# NANO_STM32F103_3.net
KiCad netlist of a schematic drawn in Altium Designer
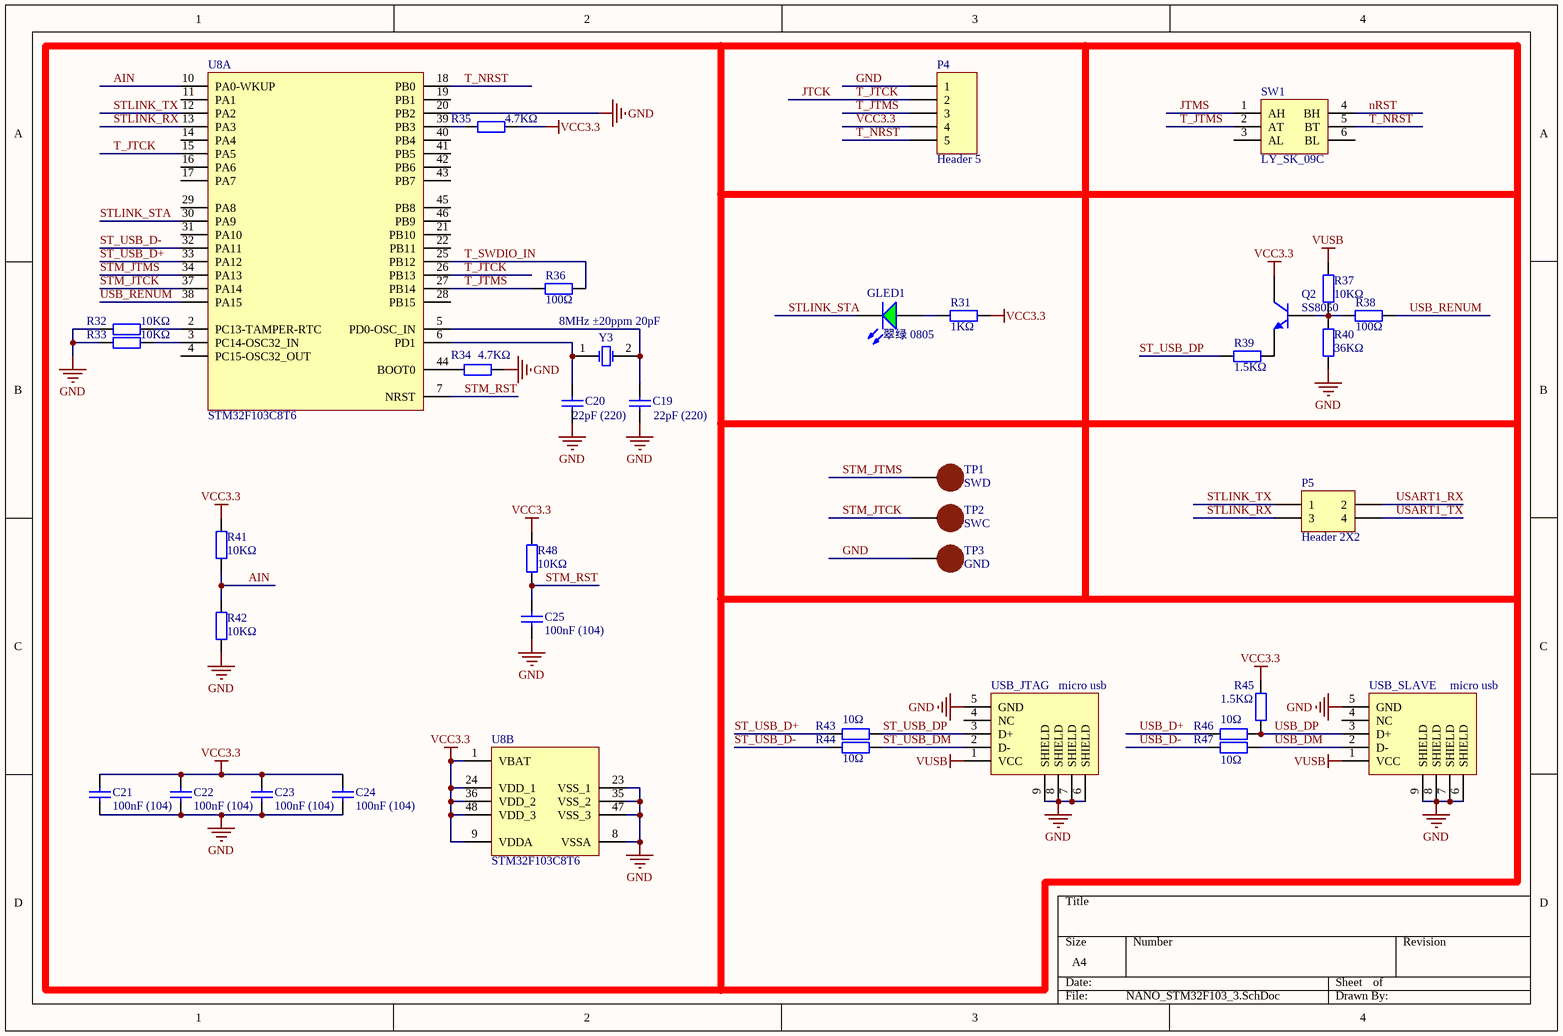
[diagram p0: NANO_STM32F103_3.SchDoc]

(export (version "E")
  (design (tool "Eeschema 10.0.6"))
  (components
    (comp (ref "C19")
      (value "22pF (220)")
      (footprint "NANO_STM32F103:0603_C")
      (description "贴片电容")
      (libsource (lib "Miscellaneous Devices LC") (part "0603 22pF (220) 5% 50V"))
    )
    (comp (ref "C20")
      (value "22pF (220)")
      (footprint "NANO_STM32F103:0603_C")
      (description "贴片电容")
      (libsource (lib "Miscellaneous Devices LC") (part "0603 22pF (220) 5% 50V"))
    )
    (comp (ref "C21")
      (value "100nF (104)")
      (footprint "NANO_STM32F103:0603_C")
      (description "贴片电容")
      (libsource (lib "Miscellaneous Devices LC") (part "0603 100nF (104) 10% 50V"))
    )
    (comp (ref "C22")
      (value "100nF (104)")
      (footprint "NANO_STM32F103:0603_C")
      (description "贴片电容")
      (libsource (lib "Miscellaneous Devices LC") (part "0603 100nF (104) 10% 50V"))
    )
    (comp (ref "C23")
      (value "100nF (104)")
      (footprint "NANO_STM32F103:0603_C")
      (description "贴片电容")
      (libsource (lib "Miscellaneous Devices LC") (part "0603 100nF (104) 10% 50V"))
    )
    (comp (ref "C24")
      (value "100nF (104)")
      (footprint "NANO_STM32F103:0603_C")
      (description "贴片电容")
      (libsource (lib "Miscellaneous Devices LC") (part "0603 100nF (104) 10% 50V"))
    )
    (comp (ref "C25")
      (value "100nF (104)")
      (footprint "NANO_STM32F103:0603_C")
      (description "贴片电容")
      (libsource (lib "Miscellaneous Devices LC") (part "0603 100nF (104) 10% 50V"))
    )
    (comp (ref "GLED1")
      (value "翠绿 0805")
      (footprint "NANO_STM32F103:0805_LED_S1")
      (description "发光二极管")
      (libsource (lib "Miscellaneous Devices LC") (part "0805 翠绿"))
    )
    (comp (ref "P4")
      (value "Header 5")
      (footprint "NANO_STM32F103:HDR1X5")
      (description "Header, 5-Pin")
      (fields (field (name "PUBLISHER") "Altium Limited"))
      (libsource (lib "Miscellaneous Connectors") (part "Header 5"))
    )
    (comp (ref "P5")
      (value "Header 2X2")
      (footprint "NANO_STM32F103:HDR2X2")
      (description "Header, 2-Pin, Dual row")
      (fields (field (name "PUBLISHER") "Altium Limited"))
      (libsource (lib "Miscellaneous Connectors") (part "Header 2X2"))
    )
    (comp (ref "Q2")
      (value "SS8050")
      (footprint "NANO_STM32F103:SOT-23(SOT-23-3)")
      (description "NPN三极管")
      (libsource (lib "Miscellaneous Devices LC") (part "SOT-23 SS8050 Y1"))
    )
    (comp (ref "R31")
      (value "1KΩ")
      (footprint "NANO_STM32F103:0603_R")
      (description "贴片电阻")
      (libsource (lib "Miscellaneous Devices LC") (part "0603 1KΩ (1001) 1%"))
    )
    (comp (ref "R32")
      (value "10KΩ")
      (footprint "NANO_STM32F103:0603_R")
      (description "贴片电阻")
      (libsource (lib "") (part "0603 10KΩ (1002) 1%_1"))
    )
    (comp (ref "R33")
      (value "10KΩ")
      (footprint "NANO_STM32F103:0603_R")
      (description "贴片电阻")
      (libsource (lib "") (part "0603 10KΩ (1002) 1%_1"))
    )
    (comp (ref "R34")
      (value "4.7KΩ")
      (footprint "NANO_STM32F103:0603_R")
      (description "贴片电阻")
      (libsource (lib "Miscellaneous Devices LC") (part "0603 4.7KΩ (4701) 1%"))
    )
    (comp (ref "R35")
      (value "4.7KΩ")
      (footprint "NANO_STM32F103:0603_R")
      (description "贴片电阻")
      (libsource (lib "Miscellaneous Devices LC") (part "0603 4.7KΩ (4701) 1%"))
    )
    (comp (ref "R36")
      (value "100Ω")
      (footprint "NANO_STM32F103:0603_R")
      (description "贴片电阻")
      (libsource (lib "Miscellaneous Devices LC") (part "0603 100Ω (1000) 1%"))
    )
    (comp (ref "R37")
      (value "10KΩ")
      (footprint "NANO_STM32F103:0603_R")
      (description "贴片电阻")
      (libsource (lib "Miscellaneous Devices LC") (part "0603 10KΩ (1002) 1%"))
    )
    (comp (ref "R38")
      (value "100Ω")
      (footprint "NANO_STM32F103:0603_R")
      (description "贴片电阻")
      (libsource (lib "Miscellaneous Devices LC") (part "0603 100Ω (1000) 1%"))
    )
    (comp (ref "R39")
      (value "1.5KΩ")
      (footprint "NANO_STM32F103:0603_R")
      (description "贴片电阻")
      (libsource (lib "") (part "0603 1.5KΩ (1501) 1%_1"))
    )
    (comp (ref "R40")
      (value "36KΩ")
      (footprint "NANO_STM32F103:0603_R")
      (description "贴片电阻")
      (libsource (lib "Miscellaneous Devices LC") (part "0603 36KΩ (3602) 1%"))
    )
    (comp (ref "R41")
      (value "10KΩ")
      (footprint "NANO_STM32F103:0603_R")
      (description "贴片电阻")
      (libsource (lib "Miscellaneous Devices LC") (part "0603 10KΩ (1002) 1%"))
    )
    (comp (ref "R42")
      (value "10KΩ")
      (footprint "NANO_STM32F103:0603_R")
      (description "贴片电阻")
      (libsource (lib "Miscellaneous Devices LC") (part "0603 10KΩ (1002) 1%"))
    )
    (comp (ref "R43")
      (value "10Ω")
      (footprint "NANO_STM32F103:0603_R")
      (description "贴片电阻")
      (libsource (lib "Miscellaneous Devices LC") (part "0603 10Ω (10R0) 1%"))
    )
    (comp (ref "R44")
      (value "10Ω")
      (footprint "NANO_STM32F103:0603_R")
      (description "贴片电阻")
      (libsource (lib "Miscellaneous Devices LC") (part "0603 10Ω (10R0) 1%"))
    )
    (comp (ref "R45")
      (value "1.5KΩ")
      (footprint "NANO_STM32F103:0603_R")
      (description "贴片电阻")
      (libsource (lib "Miscellaneous Devices LC") (part "0603 1.5KΩ (1501) 1%"))
    )
    (comp (ref "R46")
      (value "10Ω")
      (footprint "NANO_STM32F103:0603_R")
      (description "贴片电阻")
      (libsource (lib "Miscellaneous Devices LC") (part "0603 10Ω (10R0) 1%"))
    )
    (comp (ref "R47")
      (value "10Ω")
      (footprint "NANO_STM32F103:0603_R")
      (description "贴片电阻")
      (libsource (lib "Miscellaneous Devices LC") (part "0603 10Ω (10R0) 1%"))
    )
    (comp (ref "R48")
      (value "10KΩ")
      (footprint "NANO_STM32F103:0603_R")
      (description "贴片电阻")
      (libsource (lib "Miscellaneous Devices LC") (part "0603 10KΩ (1002) 1%"))
    )
    (comp (ref "SW1")
      (value "LY_SK_09C")
      (footprint "NANO_STM32F103:HDR2X3_CEN")
      (libsource (lib "NANO_STM32F103") (part "Switch_1"))
    )
    (comp (ref "TP1")
      (value "SWD")
      (footprint "NANO_STM32F103:PIN1")
      (description "圆形焊盘")
      (libsource (lib "NANO_STM32F103") (part "PAN"))
    )
    (comp (ref "TP2")
      (value "SWC")
      (footprint "NANO_STM32F103:PIN1")
      (description "圆形焊盘")
      (libsource (lib "NANO_STM32F103") (part "PAN"))
    )
    (comp (ref "TP3")
      (value "GND")
      (footprint "NANO_STM32F103:PIN1")
      (description "圆形焊盘")
      (libsource (lib "NANO_STM32F103") (part "PAN"))
    )
    (comp (ref "U8")
      (value "STM32F103C8T6")
      (footprint "NANO_STM32F103:LQFP-48_7x7x05P")
      (description "ARM")
      (libsource (lib "Miscellaneous Devices LC") (part "STM32F103C8T6"))
    )
    (comp (ref "USB_JTAG")
      (value "micro usb")
      (footprint "NANO_STM32F103:USB_Micro")
      (libsource (lib "NANO_STM32F103") (part "USB_1"))
    )
    (comp (ref "USB_SLAVE")
      (value "micro usb")
      (footprint "NANO_STM32F103:USB_Micro")
      (libsource (lib "NANO_STM32F103") (part "USB_1"))
    )
    (comp (ref "Y3")
      (value "8MHz ±20ppm 20pF")
      (footprint "NANO_STM32F103:SMD-5032_2P")
      (description "贴片晶振")
      (libsource (lib "Miscellaneous Devices LC") (part "SMD-5032_2P 8MHz 20ppm 20pF"))
    )
  )
  (nets
    (net (code "1") (name "/AIN") (class "Default")
      (node (ref "R41") (pin "1") (pinfunction "1_1") (pintype "passive"))
      (node (ref "R42") (pin "2") (pinfunction "2_2") (pintype "passive"))
      (node (ref "U8") (pin "10") (pinfunction "PA0-WKUP_10") (pintype "passive"))
    )
    (net (code "2") (name "/JTCK") (class "Default")
      (node (ref "P4") (pin "2") (pinfunction "2_2") (pintype "passive"))
      (node (ref "U8") (pin "15") (pinfunction "PA5_15") (pintype "passive"))
      (node (ref "U8") (pin "26") (pinfunction "PB13_26") (pintype "passive"))
    )
    (net (code "3") (name "/JTMS") (class "Default")
      (node (ref "SW1") (pin "1") (pinfunction "AH_1") (pintype "passive"))
    )
    (net (code "4") (name "/STLINK_RX") (class "Default")
      (node (ref "P5") (pin "3") (pinfunction "3_3") (pintype "passive"))
      (node (ref "U8") (pin "13") (pinfunction "PA3_13") (pintype "passive"))
    )
    (net (code "5") (name "/STLINK_STA") (class "Default")
      (node (ref "GLED1") (pin "K") (pinfunction "K_K") (pintype "passive"))
      (node (ref "U8") (pin "30") (pinfunction "PA9_30") (pintype "passive"))
    )
    (net (code "6") (name "/STLINK_TX") (class "Default")
      (node (ref "P5") (pin "1") (pinfunction "1_1") (pintype "passive"))
      (node (ref "U8") (pin "12") (pinfunction "PA2_12") (pintype "passive"))
    )
    (net (code "7") (name "/STM_JTCK") (class "Default")
      (node (ref "TP2") (pin "1") (pinfunction "1_1") (pintype "passive"))
      (node (ref "U8") (pin "37") (pinfunction "PA14_37") (pintype "passive"))
    )
    (net (code "8") (name "/STM_JTMS") (class "Default")
      (node (ref "TP1") (pin "1") (pinfunction "1_1") (pintype "passive"))
      (node (ref "U8") (pin "34") (pinfunction "PA13_34") (pintype "passive"))
    )
    (net (code "9") (name "/STM_RST") (class "Default")
      (node (ref "C25") (pin "1") (pinfunction "1_1") (pintype "passive"))
      (node (ref "R48") (pin "1") (pinfunction "1_1") (pintype "passive"))
      (node (ref "U8") (pin "7") (pinfunction "NRST_7") (pintype "passive"))
    )
    (net (code "10") (name "/ST_USB_D+") (class "Default")
      (node (ref "R43") (pin "1") (pinfunction "1_1") (pintype "passive"))
      (node (ref "U8") (pin "33") (pinfunction "PA12_33") (pintype "passive"))
    )
    (net (code "11") (name "/ST_USB_D-") (class "Default")
      (node (ref "R44") (pin "1") (pinfunction "1_1") (pintype "passive"))
      (node (ref "U8") (pin "32") (pinfunction "PA11_32") (pintype "passive"))
    )
    (net (code "12") (name "/ST_USB_DM") (class "Default")
      (node (ref "R44") (pin "2") (pinfunction "2_2") (pintype "passive"))
      (node (ref "USB_JTAG") (pin "2") (pinfunction "D-_2") (pintype "passive"))
    )
    (net (code "13") (name "/ST_USB_DP") (class "Default")
      (node (ref "R39") (pin "1") (pinfunction "1_1") (pintype "passive"))
      (node (ref "R43") (pin "2") (pinfunction "2_2") (pintype "passive"))
      (node (ref "USB_JTAG") (pin "3") (pinfunction "D+_3") (pintype "passive"))
    )
    (net (code "14") (name "/T_JTMS") (class "Default")
      (node (ref "P4") (pin "3") (pinfunction "3_3") (pintype "passive"))
      (node (ref "R36") (pin "1") (pinfunction "1_1") (pintype "passive"))
      (node (ref "SW1") (pin "2") (pinfunction "AT_2") (pintype "passive"))
      (node (ref "U8") (pin "27") (pinfunction "PB14_27") (pintype "passive"))
    )
    (net (code "15") (name "/T_NRST") (class "Default")
      (node (ref "P4") (pin "5") (pinfunction "5_5") (pintype "passive"))
      (node (ref "SW1") (pin "5") (pinfunction "BT_5") (pintype "passive"))
      (node (ref "U8") (pin "18") (pinfunction "PB0_18") (pintype "passive"))
    )
    (net (code "16") (name "/T_SWDIO_IN") (class "Default")
      (node (ref "R36") (pin "2") (pinfunction "2_2") (pintype "passive"))
      (node (ref "U8") (pin "25") (pinfunction "PB12_25") (pintype "passive"))
    )
    (net (code "17") (name "/USART1_RX") (class "Default")
      (node (ref "P5") (pin "2") (pinfunction "2_2") (pintype "passive"))
    )
    (net (code "18") (name "/USART1_TX") (class "Default")
      (node (ref "P5") (pin "4") (pinfunction "4_4") (pintype "passive"))
    )
    (net (code "19") (name "/USB_D+") (class "Default")
      (node (ref "R46") (pin "1") (pinfunction "1_1") (pintype "passive"))
    )
    (net (code "20") (name "/USB_D-") (class "Default")
      (node (ref "R47") (pin "1") (pinfunction "1_1") (pintype "passive"))
    )
    (net (code "21") (name "/USB_DM") (class "Default")
      (node (ref "R47") (pin "2") (pinfunction "2_2") (pintype "passive"))
      (node (ref "USB_SLAVE") (pin "2") (pinfunction "D-_2") (pintype "passive"))
    )
    (net (code "22") (name "/USB_DP") (class "Default")
      (node (ref "R45") (pin "1") (pinfunction "1_1") (pintype "passive"))
      (node (ref "R46") (pin "2") (pinfunction "2_2") (pintype "passive"))
      (node (ref "USB_SLAVE") (pin "3") (pinfunction "D+_3") (pintype "passive"))
    )
    (net (code "23") (name "/USB_RENUM") (class "Default")
      (node (ref "R38") (pin "2") (pinfunction "2_2") (pintype "passive"))
      (node (ref "U8") (pin "38") (pinfunction "PA15_38") (pintype "passive"))
    )
    (net (code "24") (name "/nRST") (class "Default")
      (node (ref "SW1") (pin "4") (pinfunction "BH_4") (pintype "passive"))
    )
    (net (code "25") (name "GND") (class "Default")
      (node (ref "C19") (pin "1") (pinfunction "1_1") (pintype "passive"))
      (node (ref "C20") (pin "1") (pinfunction "1_1") (pintype "passive"))
      (node (ref "C21") (pin "2") (pinfunction "2_2") (pintype "passive"))
      (node (ref "C22") (pin "2") (pinfunction "2_2") (pintype "passive"))
      (node (ref "C23") (pin "2") (pinfunction "2_2") (pintype "passive"))
      (node (ref "C24") (pin "2") (pinfunction "2_2") (pintype "passive"))
      (node (ref "C25") (pin "2") (pinfunction "2_2") (pintype "passive"))
      (node (ref "P4") (pin "1") (pinfunction "1_1") (pintype "passive"))
      (node (ref "R32") (pin "1") (pinfunction "1_1") (pintype "passive"))
      (node (ref "R33") (pin "1") (pinfunction "1_1") (pintype "passive"))
      (node (ref "R34") (pin "2") (pinfunction "2_2") (pintype "passive"))
      (node (ref "R40") (pin "1") (pinfunction "1_1") (pintype "passive"))
      (node (ref "R42") (pin "1") (pinfunction "1_1") (pintype "passive"))
      (node (ref "TP3") (pin "1") (pinfunction "1_1") (pintype "passive"))
      (node (ref "U8") (pin "20") (pinfunction "PB2_20") (pintype "passive"))
      (node (ref "U8") (pin "23") (pinfunction "VSS_1_23") (pintype "power_in"))
      (node (ref "U8") (pin "35") (pinfunction "VSS_2_35") (pintype "power_in"))
      (node (ref "U8") (pin "47") (pinfunction "VSS_3_47") (pintype "power_in"))
      (node (ref "U8") (pin "8") (pinfunction "VSSA_8") (pintype "power_in"))
      (node (ref "USB_JTAG") (pin "5") (pinfunction "GND_5") (pintype "passive"))
      (node (ref "USB_JTAG") (pin "6") (pinfunction "SHIELD_6") (pintype "passive"))
      (node (ref "USB_JTAG") (pin "7") (pinfunction "SHIELD_7") (pintype "passive"))
      (node (ref "USB_JTAG") (pin "8") (pinfunction "SHIELD_8") (pintype "passive"))
      (node (ref "USB_JTAG") (pin "9") (pinfunction "SHIELD_9") (pintype "passive"))
      (node (ref "USB_SLAVE") (pin "5") (pinfunction "GND_5") (pintype "passive"))
      (node (ref "USB_SLAVE") (pin "6") (pinfunction "SHIELD_6") (pintype "passive"))
      (node (ref "USB_SLAVE") (pin "7") (pinfunction "SHIELD_7") (pintype "passive"))
      (node (ref "USB_SLAVE") (pin "8") (pinfunction "SHIELD_8") (pintype "passive"))
      (node (ref "USB_SLAVE") (pin "9") (pinfunction "SHIELD_9") (pintype "passive"))
    )
    (net (code "26") (name "Net-(GLED1-PadA)") (class "Default")
      (node (ref "GLED1") (pin "A") (pinfunction "A_A") (pintype "passive"))
      (node (ref "R31") (pin "1") (pinfunction "1_1") (pintype "passive"))
    )
    (net (code "27") (name "Net-(Q2-B)") (class "Default")
      (node (ref "Q2") (pin "1") (pinfunction "B_1") (pintype "passive"))
      (node (ref "R37") (pin "1") (pinfunction "1_1") (pintype "passive"))
      (node (ref "R38") (pin "1") (pinfunction "1_1") (pintype "passive"))
      (node (ref "R40") (pin "2") (pinfunction "2_2") (pintype "passive"))
    )
    (net (code "28") (name "Net-(Q2-E)") (class "Default")
      (node (ref "Q2") (pin "2") (pinfunction "E_2") (pintype "passive"))
      (node (ref "R39") (pin "2") (pinfunction "2_2") (pintype "passive"))
    )
    (net (code "29") (name "Net-(U8A-BOOT0)") (class "Default")
      (node (ref "R34") (pin "1") (pinfunction "1_1") (pintype "passive"))
      (node (ref "U8") (pin "44") (pinfunction "BOOT0_44") (pintype "passive"))
    )
    (net (code "30") (name "Net-(U8A-PB3)") (class "Default")
      (node (ref "R35") (pin "1") (pinfunction "1_1") (pintype "passive"))
      (node (ref "U8") (pin "39") (pinfunction "PB3_39") (pintype "passive"))
    )
    (net (code "31") (name "Net-(U8A-PC13-TAMPER-RTC)") (class "Default")
      (node (ref "R32") (pin "2") (pinfunction "2_2") (pintype "passive"))
      (node (ref "U8") (pin "2") (pinfunction "PC13-TAMPER-RTC_2") (pintype "passive"))
    )
    (net (code "32") (name "Net-(U8A-PC14-OSC32_IN)") (class "Default")
      (node (ref "R33") (pin "2") (pinfunction "2_2") (pintype "passive"))
      (node (ref "U8") (pin "3") (pinfunction "PC14-OSC32_IN_3") (pintype "passive"))
    )
    (net (code "33") (name "Net-(U8A-PD0-OSC_IN)") (class "Default")
      (node (ref "C19") (pin "2") (pinfunction "2_2") (pintype "passive"))
      (node (ref "U8") (pin "5") (pinfunction "PD0-OSC_IN_5") (pintype "passive"))
      (node (ref "Y3") (pin "2") (pinfunction "OSC2_2") (pintype "passive"))
    )
    (net (code "34") (name "Net-(U8A-PD1)") (class "Default")
      (node (ref "C20") (pin "2") (pinfunction "2_2") (pintype "passive"))
      (node (ref "U8") (pin "6") (pinfunction "PD1_6") (pintype "passive"))
      (node (ref "Y3") (pin "1") (pinfunction "OSC1_1") (pintype "passive"))
    )
    (net (code "35") (name "VCC3.3") (class "Default")
      (node (ref "C21") (pin "1") (pinfunction "1_1") (pintype "passive"))
      (node (ref "C22") (pin "1") (pinfunction "1_1") (pintype "passive"))
      (node (ref "C23") (pin "1") (pinfunction "1_1") (pintype "passive"))
      (node (ref "C24") (pin "1") (pinfunction "1_1") (pintype "passive"))
      (node (ref "P4") (pin "4") (pinfunction "4_4") (pintype "passive"))
      (node (ref "Q2") (pin "3") (pinfunction "C_3") (pintype "passive"))
      (node (ref "R31") (pin "2") (pinfunction "2_2") (pintype "passive"))
      (node (ref "R35") (pin "2") (pinfunction "2_2") (pintype "passive"))
      (node (ref "R41") (pin "2") (pinfunction "2_2") (pintype "passive"))
      (node (ref "R45") (pin "2") (pinfunction "2_2") (pintype "passive"))
      (node (ref "R48") (pin "2") (pinfunction "2_2") (pintype "passive"))
      (node (ref "U8") (pin "1") (pinfunction "VBAT_1") (pintype "power_in"))
      (node (ref "U8") (pin "24") (pinfunction "VDD_1_24") (pintype "power_in"))
      (node (ref "U8") (pin "36") (pinfunction "VDD_2_36") (pintype "power_in"))
      (node (ref "U8") (pin "48") (pinfunction "VDD_3_48") (pintype "power_in"))
      (node (ref "U8") (pin "9") (pinfunction "VDDA_9") (pintype "power_in"))
    )
    (net (code "36") (name "VUSB") (class "Default")
      (node (ref "R37") (pin "2") (pinfunction "2_2") (pintype "passive"))
      (node (ref "USB_JTAG") (pin "1") (pinfunction "VCC_1") (pintype "passive"))
      (node (ref "USB_SLAVE") (pin "1") (pinfunction "VCC_1") (pintype "passive"))
    )
    (net (code "37") (name "unconnected-(SW1-AL-Pad3)") (class "Default")
      (node (ref "SW1") (pin "3") (pinfunction "AL_3") (pintype "passive"))
    )
    (net (code "38") (name "unconnected-(SW1-BL-Pad6)") (class "Default")
      (node (ref "SW1") (pin "6") (pinfunction "BL_6") (pintype "passive"))
    )
    (net (code "39") (name "unconnected-(U8A-PA1-Pad11)") (class "Default")
      (node (ref "U8") (pin "11") (pinfunction "PA1_11") (pintype "passive"))
    )
    (net (code "40") (name "unconnected-(U8A-PA4-Pad14)") (class "Default")
      (node (ref "U8") (pin "14") (pinfunction "PA4_14") (pintype "passive"))
    )
    (net (code "41") (name "unconnected-(U8A-PA6-Pad16)") (class "Default")
      (node (ref "U8") (pin "16") (pinfunction "PA6_16") (pintype "passive"))
    )
    (net (code "42") (name "unconnected-(U8A-PA7-Pad17)") (class "Default")
      (node (ref "U8") (pin "17") (pinfunction "PA7_17") (pintype "passive"))
    )
    (net (code "43") (name "unconnected-(U8A-PA8-Pad29)") (class "Default")
      (node (ref "U8") (pin "29") (pinfunction "PA8_29") (pintype "passive"))
    )
    (net (code "44") (name "unconnected-(U8A-PA10-Pad31)") (class "Default")
      (node (ref "U8") (pin "31") (pinfunction "PA10_31") (pintype "passive"))
    )
    (net (code "45") (name "unconnected-(U8A-PB1-Pad19)") (class "Default")
      (node (ref "U8") (pin "19") (pinfunction "PB1_19") (pintype "passive"))
    )
    (net (code "46") (name "unconnected-(U8A-PB4-Pad40)") (class "Default")
      (node (ref "U8") (pin "40") (pinfunction "PB4_40") (pintype "passive"))
    )
    (net (code "47") (name "unconnected-(U8A-PB5-Pad41)") (class "Default")
      (node (ref "U8") (pin "41") (pinfunction "PB5_41") (pintype "passive"))
    )
    (net (code "48") (name "unconnected-(U8A-PB6-Pad42)") (class "Default")
      (node (ref "U8") (pin "42") (pinfunction "PB6_42") (pintype "passive"))
    )
    (net (code "49") (name "unconnected-(U8A-PB7-Pad43)") (class "Default")
      (node (ref "U8") (pin "43") (pinfunction "PB7_43") (pintype "passive"))
    )
    (net (code "50") (name "unconnected-(U8A-PB8-Pad45)") (class "Default")
      (node (ref "U8") (pin "45") (pinfunction "PB8_45") (pintype "passive"))
    )
    (net (code "51") (name "unconnected-(U8A-PB9-Pad46)") (class "Default")
      (node (ref "U8") (pin "46") (pinfunction "PB9_46") (pintype "passive"))
    )
    (net (code "52") (name "unconnected-(U8A-PB10-Pad21)") (class "Default")
      (node (ref "U8") (pin "21") (pinfunction "PB10_21") (pintype "passive"))
    )
    (net (code "53") (name "unconnected-(U8A-PB11-Pad22)") (class "Default")
      (node (ref "U8") (pin "22") (pinfunction "PB11_22") (pintype "passive"))
    )
    (net (code "54") (name "unconnected-(U8A-PB15-Pad28)") (class "Default")
      (node (ref "U8") (pin "28") (pinfunction "PB15_28") (pintype "passive"))
    )
    (net (code "55") (name "unconnected-(U8A-PC15-OSC32_OUT-Pad4)") (class "Default")
      (node (ref "U8") (pin "4") (pinfunction "PC15-OSC32_OUT_4") (pintype "passive"))
    )
    (net (code "56") (name "unconnected-(USB_JTAG-NC-Pad4)") (class "Default")
      (node (ref "USB_JTAG") (pin "4") (pinfunction "NC_4") (pintype "passive"))
    )
    (net (code "57") (name "unconnected-(USB_SLAVE-NC-Pad4)") (class "Default")
      (node (ref "USB_SLAVE") (pin "4") (pinfunction "NC_4") (pintype "passive"))
    )
  )
)
